# MCU.net
KiCad netlist of a schematic drawn in EAGLE
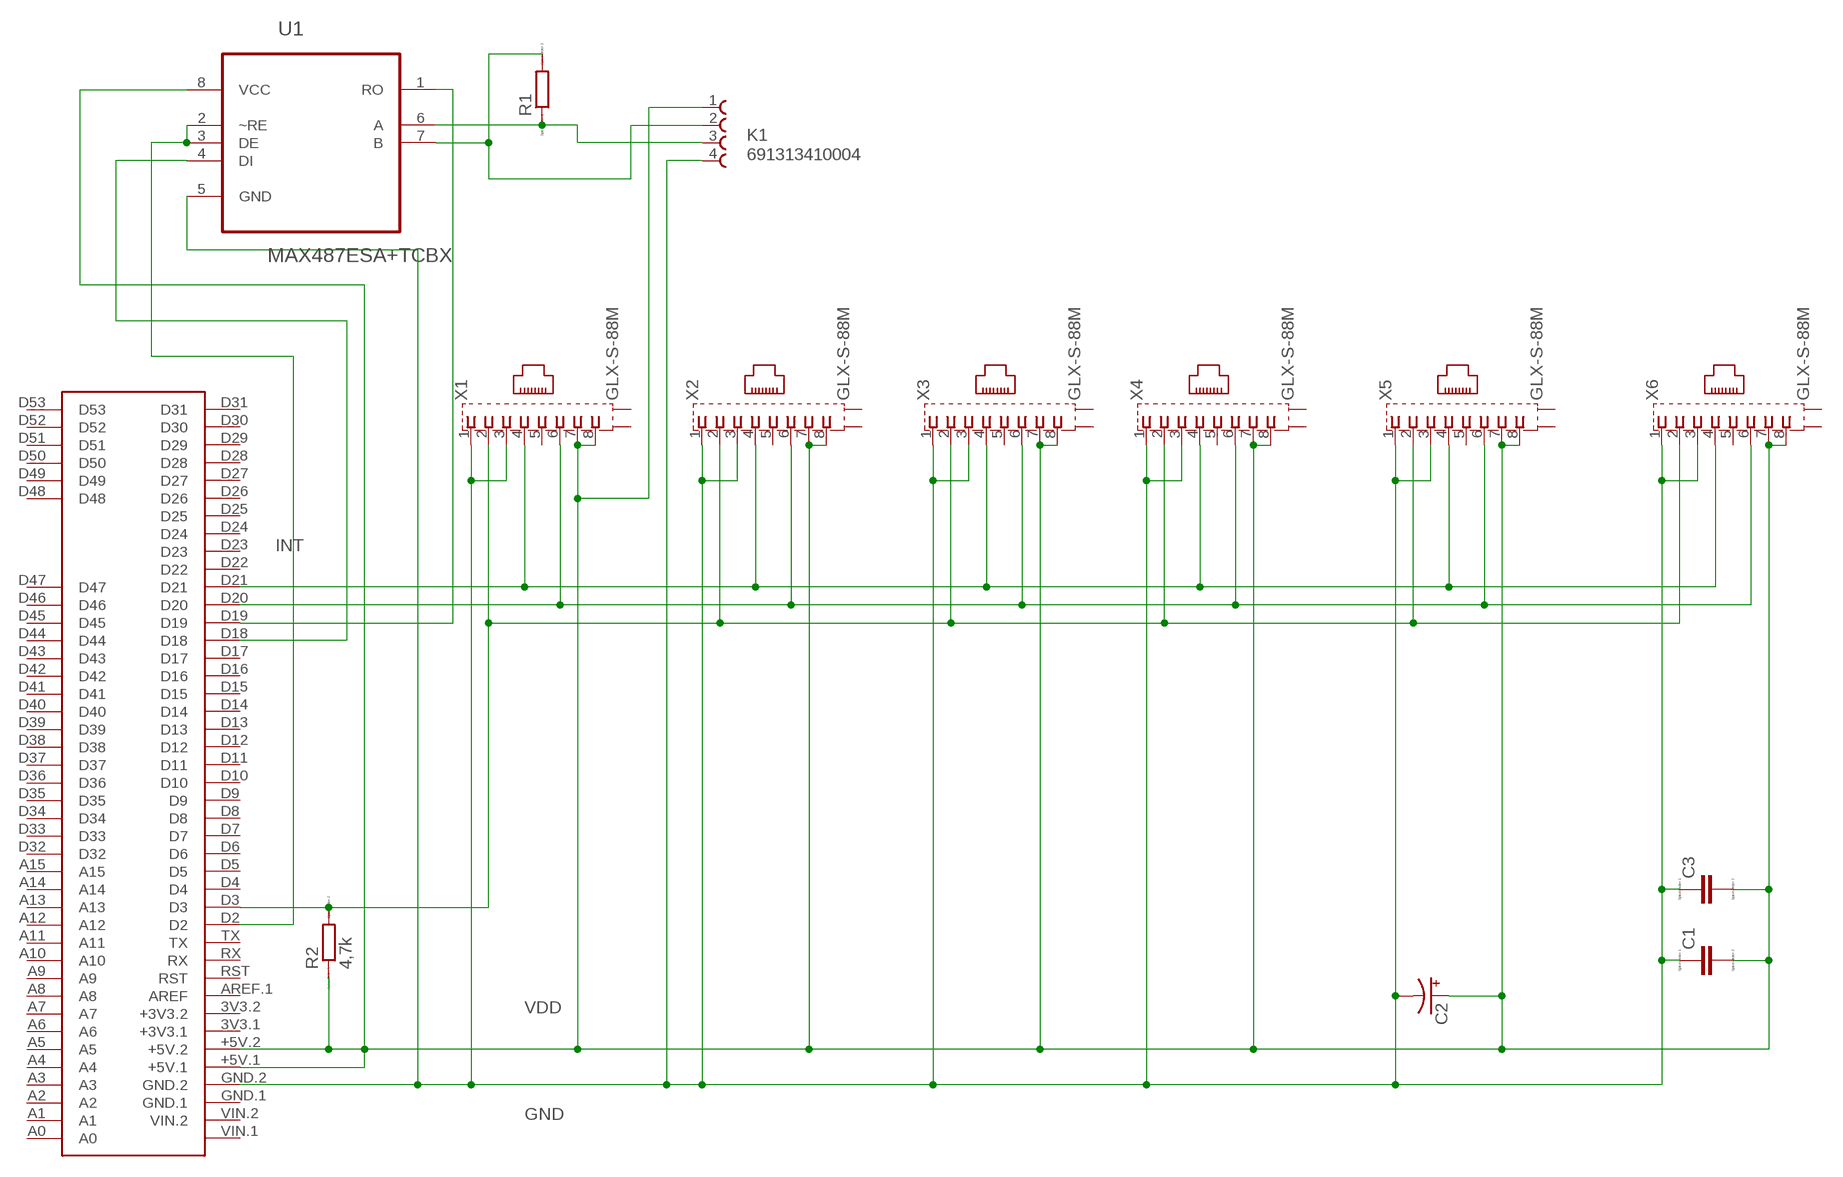
[diagram p0: schematic, sheet 1]

(export (version "E")
  (design (tool "Eeschema 10.0.6"))
  (components
    (comp (ref "C1")
      (value "CC1206")
      (footprint "eagle-import:C1206")
      (libsource (lib "eagle-import") (part "CC1206"))
    )
    (comp (ref "C2")
      (value "CPOL-US153CLV-0807")
      (footprint "eagle-import:153CLV-0807")
      (libsource (lib "eagle-import") (part "CPOL-US153CLV-0807"))
    )
    (comp (ref "C3")
      (value "CC1206")
      (footprint "eagle-import:C1206")
      (libsource (lib "eagle-import") (part "CC1206"))
    )
    (comp (ref "K1")
      (value "691313410004")
      (footprint "eagle-import:691313410004")
      (libsource (lib "eagle-import") (part "691313410004"))
    )
    (comp (ref "R1")
      (value "RR1206")
      (footprint "eagle-import:R1206")
      (libsource (lib "eagle-import") (part "RR1206"))
    )
    (comp (ref "R2")
      (value "4,7k")
      (footprint "eagle-import:R1206")
      (libsource (lib "eagle-import") (part "RR1206"))
    )
    (comp (ref "U$1")
      (value "MEGA2560_MIKRO")
      (footprint "eagle-import:MEGA2560_MIKRO")
      (libsource (lib "eagle-import") (part "MEGA2560_MIKRO"))
    )
    (comp (ref "U1")
      (value "MAX487ESA+TCBX")
      (footprint "eagle-import:SOIC127P600X175-8N")
      (fields (field (name "MF") "Maxim Integrated"))
      (libsource (lib "eagle-import") (part "MAX487ESA+TCBX"))
    )
    (comp (ref "X1")
      (value "GLX-S-88M")
      (footprint "eagle-import:GLX-S-88M")
      (libsource (lib "eagle-import") (part "GLX-S-88M"))
    )
    (comp (ref "X2")
      (value "GLX-S-88M")
      (footprint "eagle-import:GLX-S-88M")
      (libsource (lib "eagle-import") (part "GLX-S-88M"))
    )
    (comp (ref "X3")
      (value "GLX-S-88M")
      (footprint "eagle-import:GLX-S-88M")
      (libsource (lib "eagle-import") (part "GLX-S-88M"))
    )
    (comp (ref "X4")
      (value "GLX-S-88M")
      (footprint "eagle-import:GLX-S-88M")
      (libsource (lib "eagle-import") (part "GLX-S-88M"))
    )
    (comp (ref "X5")
      (value "GLX-S-88M")
      (footprint "eagle-import:GLX-S-88M")
      (libsource (lib "eagle-import") (part "GLX-S-88M"))
    )
    (comp (ref "X6")
      (value "GLX-S-88M")
      (footprint "eagle-import:GLX-S-88M")
      (libsource (lib "eagle-import") (part "GLX-S-88M"))
    )
  )
  (nets
    (net (code "1") (name "/GND") (class "Default")
      (node (ref "C1") (pin "1") (pinfunction "1_1") (pintype "passive"))
      (node (ref "C2") (pin "-") (pinfunction "-_-") (pintype "passive"))
      (node (ref "C3") (pin "1") (pinfunction "1_1") (pintype "passive"))
      (node (ref "K1") (pin "4") (pinfunction "4_4") (pintype "passive"))
      (node (ref "U$1") (pin "GND.2") (pinfunction "GND.2_GND.2") (pintype "bidirectional"))
      (node (ref "U1") (pin "5") (pinfunction "GND_5") (pintype "passive"))
      (node (ref "X1") (pin "1") (pinfunction "1_1") (pintype "passive"))
      (node (ref "X1") (pin "3") (pinfunction "3_3") (pintype "passive"))
      (node (ref "X2") (pin "1") (pinfunction "1_1") (pintype "passive"))
      (node (ref "X2") (pin "3") (pinfunction "3_3") (pintype "passive"))
      (node (ref "X3") (pin "1") (pinfunction "1_1") (pintype "passive"))
      (node (ref "X3") (pin "3") (pinfunction "3_3") (pintype "passive"))
      (node (ref "X4") (pin "1") (pinfunction "1_1") (pintype "passive"))
      (node (ref "X4") (pin "3") (pinfunction "3_3") (pintype "passive"))
      (node (ref "X5") (pin "1") (pinfunction "1_1") (pintype "passive"))
      (node (ref "X5") (pin "3") (pinfunction "3_3") (pintype "passive"))
      (node (ref "X6") (pin "1") (pinfunction "1_1") (pintype "passive"))
      (node (ref "X6") (pin "3") (pinfunction "3_3") (pintype "passive"))
    )
    (net (code "2") (name "/INT") (class "Default")
      (node (ref "R2") (pin "2") (pinfunction "2_2") (pintype "passive"))
      (node (ref "U$1") (pin "D3") (pinfunction "D3_D3") (pintype "bidirectional"))
      (node (ref "X1") (pin "2") (pinfunction "2_2") (pintype "passive"))
      (node (ref "X2") (pin "2") (pinfunction "2_2") (pintype "passive"))
      (node (ref "X3") (pin "2") (pinfunction "2_2") (pintype "passive"))
      (node (ref "X4") (pin "2") (pinfunction "2_2") (pintype "passive"))
      (node (ref "X5") (pin "2") (pinfunction "2_2") (pintype "passive"))
      (node (ref "X6") (pin "2") (pinfunction "2_2") (pintype "passive"))
    )
    (net (code "3") (name "/VDD") (class "Default")
      (node (ref "C1") (pin "2") (pinfunction "2_2") (pintype "passive"))
      (node (ref "C2") (pin "+") (pinfunction "+_+") (pintype "passive"))
      (node (ref "C3") (pin "2") (pinfunction "2_2") (pintype "passive"))
      (node (ref "K1") (pin "1") (pinfunction "1_1") (pintype "passive"))
      (node (ref "R2") (pin "1") (pinfunction "1_1") (pintype "passive"))
      (node (ref "U$1") (pin "+5V.1") (pinfunction "+5V.1_+5V.1") (pintype "bidirectional"))
      (node (ref "U$1") (pin "+5V.2") (pinfunction "+5V.2_+5V.2") (pintype "bidirectional"))
      (node (ref "U1") (pin "8") (pinfunction "VCC_8") (pintype "power_in"))
      (node (ref "X1") (pin "7") (pinfunction "7_7") (pintype "passive"))
      (node (ref "X1") (pin "8") (pinfunction "8_8") (pintype "passive"))
      (node (ref "X2") (pin "7") (pinfunction "7_7") (pintype "passive"))
      (node (ref "X2") (pin "8") (pinfunction "8_8") (pintype "passive"))
      (node (ref "X3") (pin "7") (pinfunction "7_7") (pintype "passive"))
      (node (ref "X3") (pin "8") (pinfunction "8_8") (pintype "passive"))
      (node (ref "X4") (pin "7") (pinfunction "7_7") (pintype "passive"))
      (node (ref "X4") (pin "8") (pinfunction "8_8") (pintype "passive"))
      (node (ref "X5") (pin "7") (pinfunction "7_7") (pintype "passive"))
      (node (ref "X5") (pin "8") (pinfunction "8_8") (pintype "passive"))
      (node (ref "X6") (pin "7") (pinfunction "7_7") (pintype "passive"))
      (node (ref "X6") (pin "8") (pinfunction "8_8") (pintype "passive"))
    )
    (net (code "4") (name "Net-(U$1-PadD20)") (class "Default")
      (node (ref "U$1") (pin "D20") (pinfunction "D20_D20") (pintype "bidirectional"))
      (node (ref "X1") (pin "6") (pinfunction "6_6") (pintype "passive"))
      (node (ref "X2") (pin "6") (pinfunction "6_6") (pintype "passive"))
      (node (ref "X3") (pin "6") (pinfunction "6_6") (pintype "passive"))
      (node (ref "X4") (pin "6") (pinfunction "6_6") (pintype "passive"))
      (node (ref "X5") (pin "6") (pinfunction "6_6") (pintype "passive"))
      (node (ref "X6") (pin "6") (pinfunction "6_6") (pintype "passive"))
    )
    (net (code "5") (name "Net-(U$1-PadD21)") (class "Default")
      (node (ref "U$1") (pin "D21") (pinfunction "D21_D21") (pintype "bidirectional"))
      (node (ref "X1") (pin "4") (pinfunction "4_4") (pintype "passive"))
      (node (ref "X2") (pin "4") (pinfunction "4_4") (pintype "passive"))
      (node (ref "X3") (pin "4") (pinfunction "4_4") (pintype "passive"))
      (node (ref "X4") (pin "4") (pinfunction "4_4") (pintype "passive"))
      (node (ref "X5") (pin "4") (pinfunction "4_4") (pintype "passive"))
      (node (ref "X6") (pin "4") (pinfunction "4_4") (pintype "passive"))
    )
    (net (code "6") (name "Net-(U1-A)") (class "Default")
      (node (ref "K1") (pin "3") (pinfunction "3_3") (pintype "passive"))
      (node (ref "R1") (pin "1") (pinfunction "1_1") (pintype "passive"))
      (node (ref "U1") (pin "6") (pinfunction "A_6") (pintype "bidirectional"))
    )
    (net (code "7") (name "Net-(U1-B)") (class "Default")
      (node (ref "K1") (pin "2") (pinfunction "2_2") (pintype "passive"))
      (node (ref "R1") (pin "2") (pinfunction "2_2") (pintype "passive"))
      (node (ref "U1") (pin "7") (pinfunction "B_7") (pintype "bidirectional"))
    )
    (net (code "8") (name "Net-(U1-DE)") (class "Default")
      (node (ref "U$1") (pin "D2") (pinfunction "D2_D2") (pintype "bidirectional"))
      (node (ref "U1") (pin "2") (pinfunction "~{RE}_2") (pintype "input"))
      (node (ref "U1") (pin "3") (pinfunction "DE_3") (pintype "input"))
    )
    (net (code "9") (name "Net-(U1-DI)") (class "Default")
      (node (ref "U$1") (pin "D18") (pinfunction "D18_D18") (pintype "bidirectional"))
      (node (ref "U1") (pin "4") (pinfunction "DI_4") (pintype "input"))
    )
    (net (code "10") (name "Net-(U1-RO)") (class "Default")
      (node (ref "U$1") (pin "D19") (pinfunction "D19_D19") (pintype "bidirectional"))
      (node (ref "U1") (pin "1") (pinfunction "RO_1") (pintype "output"))
    )
    (net (code "11") (name "unconnected-(U$1-+3V3.1-Pad3V3.1)") (class "Default")
      (node (ref "U$1") (pin "3V3.1") (pinfunction "+3V3.1_3V3.1") (pintype "bidirectional"))
    )
    (net (code "12") (name "unconnected-(U$1-+3V3.2-Pad3V3.2)") (class "Default")
      (node (ref "U$1") (pin "3V3.2") (pinfunction "+3V3.2_3V3.2") (pintype "bidirectional"))
    )
    (net (code "13") (name "unconnected-(U$1-AREF-PadAREF.1)") (class "Default")
      (node (ref "U$1") (pin "AREF.1") (pinfunction "AREF_AREF.1") (pintype "bidirectional"))
    )
    (net (code "14") (name "unconnected-(U$1-PadA0)") (class "Default")
      (node (ref "U$1") (pin "A0") (pinfunction "A0_A0") (pintype "bidirectional"))
    )
    (net (code "15") (name "unconnected-(U$1-PadA1)") (class "Default")
      (node (ref "U$1") (pin "A1") (pinfunction "A1_A1") (pintype "bidirectional"))
    )
    (net (code "16") (name "unconnected-(U$1-PadA2)") (class "Default")
      (node (ref "U$1") (pin "A2") (pinfunction "A2_A2") (pintype "bidirectional"))
    )
    (net (code "17") (name "unconnected-(U$1-PadA3)") (class "Default")
      (node (ref "U$1") (pin "A3") (pinfunction "A3_A3") (pintype "bidirectional"))
    )
    (net (code "18") (name "unconnected-(U$1-PadA4)") (class "Default")
      (node (ref "U$1") (pin "A4") (pinfunction "A4_A4") (pintype "bidirectional"))
    )
    (net (code "19") (name "unconnected-(U$1-PadA5)") (class "Default")
      (node (ref "U$1") (pin "A5") (pinfunction "A5_A5") (pintype "bidirectional"))
    )
    (net (code "20") (name "unconnected-(U$1-PadA6)") (class "Default")
      (node (ref "U$1") (pin "A6") (pinfunction "A6_A6") (pintype "bidirectional"))
    )
    (net (code "21") (name "unconnected-(U$1-PadA7)") (class "Default")
      (node (ref "U$1") (pin "A7") (pinfunction "A7_A7") (pintype "bidirectional"))
    )
    (net (code "22") (name "unconnected-(U$1-PadA8)") (class "Default")
      (node (ref "U$1") (pin "A8") (pinfunction "A8_A8") (pintype "bidirectional"))
    )
    (net (code "23") (name "unconnected-(U$1-PadA9)") (class "Default")
      (node (ref "U$1") (pin "A9") (pinfunction "A9_A9") (pintype "bidirectional"))
    )
    (net (code "24") (name "unconnected-(U$1-PadA10)") (class "Default")
      (node (ref "U$1") (pin "A10") (pinfunction "A10_A10") (pintype "bidirectional"))
    )
    (net (code "25") (name "unconnected-(U$1-PadA11)") (class "Default")
      (node (ref "U$1") (pin "A11") (pinfunction "A11_A11") (pintype "bidirectional"))
    )
    (net (code "26") (name "unconnected-(U$1-PadA12)") (class "Default")
      (node (ref "U$1") (pin "A12") (pinfunction "A12_A12") (pintype "bidirectional"))
    )
    (net (code "27") (name "unconnected-(U$1-PadA13)") (class "Default")
      (node (ref "U$1") (pin "A13") (pinfunction "A13_A13") (pintype "bidirectional"))
    )
    (net (code "28") (name "unconnected-(U$1-PadA14)") (class "Default")
      (node (ref "U$1") (pin "A14") (pinfunction "A14_A14") (pintype "bidirectional"))
    )
    (net (code "29") (name "unconnected-(U$1-PadA15)") (class "Default")
      (node (ref "U$1") (pin "A15") (pinfunction "A15_A15") (pintype "bidirectional"))
    )
    (net (code "30") (name "unconnected-(U$1-PadD4)") (class "Default")
      (node (ref "U$1") (pin "D4") (pinfunction "D4_D4") (pintype "bidirectional"))
    )
    (net (code "31") (name "unconnected-(U$1-PadD5)") (class "Default")
      (node (ref "U$1") (pin "D5") (pinfunction "D5_D5") (pintype "bidirectional"))
    )
    (net (code "32") (name "unconnected-(U$1-PadD6)") (class "Default")
      (node (ref "U$1") (pin "D6") (pinfunction "D6_D6") (pintype "bidirectional"))
    )
    (net (code "33") (name "unconnected-(U$1-PadD7)") (class "Default")
      (node (ref "U$1") (pin "D7") (pinfunction "D7_D7") (pintype "bidirectional"))
    )
    (net (code "34") (name "unconnected-(U$1-PadD8)") (class "Default")
      (node (ref "U$1") (pin "D8") (pinfunction "D8_D8") (pintype "bidirectional"))
    )
    (net (code "35") (name "unconnected-(U$1-PadD9)") (class "Default")
      (node (ref "U$1") (pin "D9") (pinfunction "D9_D9") (pintype "bidirectional"))
    )
    (net (code "36") (name "unconnected-(U$1-PadD10)") (class "Default")
      (node (ref "U$1") (pin "D10") (pinfunction "D10_D10") (pintype "bidirectional"))
    )
    (net (code "37") (name "unconnected-(U$1-PadD11)") (class "Default")
      (node (ref "U$1") (pin "D11") (pinfunction "D11_D11") (pintype "bidirectional"))
    )
    (net (code "38") (name "unconnected-(U$1-PadD12)") (class "Default")
      (node (ref "U$1") (pin "D12") (pinfunction "D12_D12") (pintype "bidirectional"))
    )
    (net (code "39") (name "unconnected-(U$1-PadD13)") (class "Default")
      (node (ref "U$1") (pin "D13") (pinfunction "D13_D13") (pintype "bidirectional"))
    )
    (net (code "40") (name "unconnected-(U$1-PadD14)") (class "Default")
      (node (ref "U$1") (pin "D14") (pinfunction "D14_D14") (pintype "bidirectional"))
    )
    (net (code "41") (name "unconnected-(U$1-PadD15)") (class "Default")
      (node (ref "U$1") (pin "D15") (pinfunction "D15_D15") (pintype "bidirectional"))
    )
    (net (code "42") (name "unconnected-(U$1-PadD16)") (class "Default")
      (node (ref "U$1") (pin "D16") (pinfunction "D16_D16") (pintype "bidirectional"))
    )
    (net (code "43") (name "unconnected-(U$1-PadD17)") (class "Default")
      (node (ref "U$1") (pin "D17") (pinfunction "D17_D17") (pintype "bidirectional"))
    )
    (net (code "44") (name "unconnected-(U$1-PadD22)") (class "Default")
      (node (ref "U$1") (pin "D22") (pinfunction "D22_D22") (pintype "bidirectional"))
    )
    (net (code "45") (name "unconnected-(U$1-PadD23)") (class "Default")
      (node (ref "U$1") (pin "D23") (pinfunction "D23_D23") (pintype "bidirectional"))
    )
    (net (code "46") (name "unconnected-(U$1-PadD24)") (class "Default")
      (node (ref "U$1") (pin "D24") (pinfunction "D24_D24") (pintype "bidirectional"))
    )
    (net (code "47") (name "unconnected-(U$1-PadD25)") (class "Default")
      (node (ref "U$1") (pin "D25") (pinfunction "D25_D25") (pintype "bidirectional"))
    )
    (net (code "48") (name "unconnected-(U$1-PadD26)") (class "Default")
      (node (ref "U$1") (pin "D26") (pinfunction "D26_D26") (pintype "bidirectional"))
    )
    (net (code "49") (name "unconnected-(U$1-PadD27)") (class "Default")
      (node (ref "U$1") (pin "D27") (pinfunction "D27_D27") (pintype "bidirectional"))
    )
    (net (code "50") (name "unconnected-(U$1-PadD28)") (class "Default")
      (node (ref "U$1") (pin "D28") (pinfunction "D28_D28") (pintype "bidirectional"))
    )
    (net (code "51") (name "unconnected-(U$1-PadD29)") (class "Default")
      (node (ref "U$1") (pin "D29") (pinfunction "D29_D29") (pintype "bidirectional"))
    )
    (net (code "52") (name "unconnected-(U$1-PadD30)") (class "Default")
      (node (ref "U$1") (pin "D30") (pinfunction "D30_D30") (pintype "bidirectional"))
    )
    (net (code "53") (name "unconnected-(U$1-PadD31)") (class "Default")
      (node (ref "U$1") (pin "D31") (pinfunction "D31_D31") (pintype "bidirectional"))
    )
    (net (code "54") (name "unconnected-(U$1-PadD32)") (class "Default")
      (node (ref "U$1") (pin "D32") (pinfunction "D32_D32") (pintype "bidirectional"))
    )
    (net (code "55") (name "unconnected-(U$1-PadD33)") (class "Default")
      (node (ref "U$1") (pin "D33") (pinfunction "D33_D33") (pintype "bidirectional"))
    )
    (net (code "56") (name "unconnected-(U$1-PadD34)") (class "Default")
      (node (ref "U$1") (pin "D34") (pinfunction "D34_D34") (pintype "bidirectional"))
    )
    (net (code "57") (name "unconnected-(U$1-PadD35)") (class "Default")
      (node (ref "U$1") (pin "D35") (pinfunction "D35_D35") (pintype "bidirectional"))
    )
    (net (code "58") (name "unconnected-(U$1-PadD36)") (class "Default")
      (node (ref "U$1") (pin "D36") (pinfunction "D36_D36") (pintype "bidirectional"))
    )
    (net (code "59") (name "unconnected-(U$1-PadD37)") (class "Default")
      (node (ref "U$1") (pin "D37") (pinfunction "D37_D37") (pintype "bidirectional"))
    )
    (net (code "60") (name "unconnected-(U$1-PadD38)") (class "Default")
      (node (ref "U$1") (pin "D38") (pinfunction "D38_D38") (pintype "bidirectional"))
    )
    (net (code "61") (name "unconnected-(U$1-PadD39)") (class "Default")
      (node (ref "U$1") (pin "D39") (pinfunction "D39_D39") (pintype "bidirectional"))
    )
    (net (code "62") (name "unconnected-(U$1-PadD40)") (class "Default")
      (node (ref "U$1") (pin "D40") (pinfunction "D40_D40") (pintype "bidirectional"))
    )
    (net (code "63") (name "unconnected-(U$1-PadD41)") (class "Default")
      (node (ref "U$1") (pin "D41") (pinfunction "D41_D41") (pintype "bidirectional"))
    )
    (net (code "64") (name "unconnected-(U$1-PadD42)") (class "Default")
      (node (ref "U$1") (pin "D42") (pinfunction "D42_D42") (pintype "bidirectional"))
    )
    (net (code "65") (name "unconnected-(U$1-PadD43)") (class "Default")
      (node (ref "U$1") (pin "D43") (pinfunction "D43_D43") (pintype "bidirectional"))
    )
    (net (code "66") (name "unconnected-(U$1-PadD44)") (class "Default")
      (node (ref "U$1") (pin "D44") (pinfunction "D44_D44") (pintype "bidirectional"))
    )
    (net (code "67") (name "unconnected-(U$1-PadD45)") (class "Default")
      (node (ref "U$1") (pin "D45") (pinfunction "D45_D45") (pintype "bidirectional"))
    )
    (net (code "68") (name "unconnected-(U$1-PadD46)") (class "Default")
      (node (ref "U$1") (pin "D46") (pinfunction "D46_D46") (pintype "bidirectional"))
    )
    (net (code "69") (name "unconnected-(U$1-PadD47)") (class "Default")
      (node (ref "U$1") (pin "D47") (pinfunction "D47_D47") (pintype "bidirectional"))
    )
    (net (code "70") (name "unconnected-(U$1-PadD48)") (class "Default")
      (node (ref "U$1") (pin "D48") (pinfunction "D48_D48") (pintype "bidirectional"))
    )
    (net (code "71") (name "unconnected-(U$1-PadD49)") (class "Default")
      (node (ref "U$1") (pin "D49") (pinfunction "D49_D49") (pintype "bidirectional"))
    )
    (net (code "72") (name "unconnected-(U$1-PadD50)") (class "Default")
      (node (ref "U$1") (pin "D50") (pinfunction "D50_D50") (pintype "bidirectional"))
    )
    (net (code "73") (name "unconnected-(U$1-PadD51)") (class "Default")
      (node (ref "U$1") (pin "D51") (pinfunction "D51_D51") (pintype "bidirectional"))
    )
    (net (code "74") (name "unconnected-(U$1-PadD52)") (class "Default")
      (node (ref "U$1") (pin "D52") (pinfunction "D52_D52") (pintype "bidirectional"))
    )
    (net (code "75") (name "unconnected-(U$1-PadD53)") (class "Default")
      (node (ref "U$1") (pin "D53") (pinfunction "D53_D53") (pintype "bidirectional"))
    )
    (net (code "76") (name "unconnected-(U$1-PadGND.1)") (class "Default")
      (node (ref "U$1") (pin "GND.1") (pinfunction "GND.1_GND.1") (pintype "bidirectional"))
    )
    (net (code "77") (name "unconnected-(U$1-PadRST)") (class "Default")
      (node (ref "U$1") (pin "RST") (pinfunction "RST_RST") (pintype "bidirectional"))
    )
    (net (code "78") (name "unconnected-(U$1-PadRX)") (class "Default")
      (node (ref "U$1") (pin "RX") (pinfunction "RX_RX") (pintype "bidirectional"))
    )
    (net (code "79") (name "unconnected-(U$1-PadTX)") (class "Default")
      (node (ref "U$1") (pin "TX") (pinfunction "TX_TX") (pintype "bidirectional"))
    )
    (net (code "80") (name "unconnected-(U$1-PadVIN.1)") (class "Default")
      (node (ref "U$1") (pin "VIN.1") (pinfunction "VIN.1_VIN.1") (pintype "bidirectional"))
    )
    (net (code "81") (name "unconnected-(U$1-PadVIN.2)") (class "Default")
      (node (ref "U$1") (pin "VIN.2") (pinfunction "VIN.2_VIN.2") (pintype "bidirectional"))
    )
    (net (code "82") (name "unconnected-(X1-Pad5)") (class "Default")
      (node (ref "X1") (pin "5") (pinfunction "5_5") (pintype "passive"))
    )
    (net (code "83") (name "unconnected-(X1-PadS1)") (class "Default")
      (node (ref "X1") (pin "S1") (pinfunction "S1_S1") (pintype "passive"))
    )
    (net (code "84") (name "unconnected-(X1-PadS2)") (class "Default")
      (node (ref "X1") (pin "S2") (pinfunction "S2_S2") (pintype "passive"))
    )
    (net (code "85") (name "unconnected-(X2-Pad5)") (class "Default")
      (node (ref "X2") (pin "5") (pinfunction "5_5") (pintype "passive"))
    )
    (net (code "86") (name "unconnected-(X2-PadS1)") (class "Default")
      (node (ref "X2") (pin "S1") (pinfunction "S1_S1") (pintype "passive"))
    )
    (net (code "87") (name "unconnected-(X2-PadS2)") (class "Default")
      (node (ref "X2") (pin "S2") (pinfunction "S2_S2") (pintype "passive"))
    )
    (net (code "88") (name "unconnected-(X3-Pad5)") (class "Default")
      (node (ref "X3") (pin "5") (pinfunction "5_5") (pintype "passive"))
    )
    (net (code "89") (name "unconnected-(X3-PadS1)") (class "Default")
      (node (ref "X3") (pin "S1") (pinfunction "S1_S1") (pintype "passive"))
    )
    (net (code "90") (name "unconnected-(X3-PadS2)") (class "Default")
      (node (ref "X3") (pin "S2") (pinfunction "S2_S2") (pintype "passive"))
    )
    (net (code "91") (name "unconnected-(X4-Pad5)") (class "Default")
      (node (ref "X4") (pin "5") (pinfunction "5_5") (pintype "passive"))
    )
    (net (code "92") (name "unconnected-(X4-PadS1)") (class "Default")
      (node (ref "X4") (pin "S1") (pinfunction "S1_S1") (pintype "passive"))
    )
    (net (code "93") (name "unconnected-(X4-PadS2)") (class "Default")
      (node (ref "X4") (pin "S2") (pinfunction "S2_S2") (pintype "passive"))
    )
    (net (code "94") (name "unconnected-(X5-Pad5)") (class "Default")
      (node (ref "X5") (pin "5") (pinfunction "5_5") (pintype "passive"))
    )
    (net (code "95") (name "unconnected-(X5-PadS1)") (class "Default")
      (node (ref "X5") (pin "S1") (pinfunction "S1_S1") (pintype "passive"))
    )
    (net (code "96") (name "unconnected-(X5-PadS2)") (class "Default")
      (node (ref "X5") (pin "S2") (pinfunction "S2_S2") (pintype "passive"))
    )
    (net (code "97") (name "unconnected-(X6-Pad5)") (class "Default")
      (node (ref "X6") (pin "5") (pinfunction "5_5") (pintype "passive"))
    )
    (net (code "98") (name "unconnected-(X6-PadS1)") (class "Default")
      (node (ref "X6") (pin "S1") (pinfunction "S1_S1") (pintype "passive"))
    )
    (net (code "99") (name "unconnected-(X6-PadS2)") (class "Default")
      (node (ref "X6") (pin "S2") (pinfunction "S2_S2") (pintype "passive"))
    )
  )
)
